# battery_buzzer.net
KiCad netlist of a schematic drawn in EAGLE
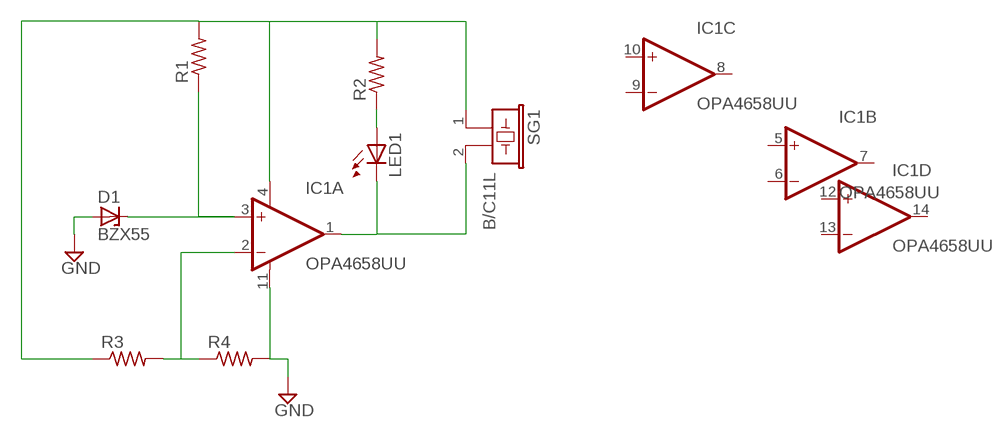
[diagram p0: schematic, sheet 1]

(export (version "E")
  (design (tool "Eeschema 10.0.6"))
  (components
    (comp (ref "D1")
      (value "BZX55")
      (footprint "eagle-import:DO35Z10")
      (libsource (lib "eagle-import") (part "BZX55"))
    )
    (comp (ref "IC1")
      (value "OPA4658UU")
      (footprint "eagle-import:SO14")
      (libsource (lib "eagle-import") (part "OPA4658UU"))
    )
    (comp (ref "LED1")
      (value "LED-FKIT-1206")
      (footprint "eagle-import:FKIT-LED-1206")
      (libsource (lib "eagle-import") (part "LED-FKIT-1206"))
    )
    (comp (ref "R1")
      (value "R-US_R0603")
      (footprint "eagle-import:R0603")
      (libsource (lib "eagle-import") (part "R-US_R0603"))
    )
    (comp (ref "R2")
      (value "R-US_R0603")
      (footprint "eagle-import:R0603")
      (libsource (lib "eagle-import") (part "R-US_R0603"))
    )
    (comp (ref "R3")
      (value "R-US_R0603")
      (footprint "eagle-import:R0603")
      (libsource (lib "eagle-import") (part "R-US_R0603"))
    )
    (comp (ref "R4")
      (value "R-US_R0603")
      (footprint "eagle-import:R0603")
      (libsource (lib "eagle-import") (part "R-US_R0603"))
    )
    (comp (ref "SG1")
      (value "B/C11L")
      (footprint "eagle-import:B_C11L")
      (libsource (lib "eagle-import") (part "B/C11L"))
    )
  )
  (nets
    (net (code "1") (name "GND") (class "Default")
      (node (ref "D1") (pin "A") (pinfunction "A_A") (pintype "passive"))
      (node (ref "IC1") (pin "11") (pinfunction "V-_11") (pintype "power_in"))
      (node (ref "R4") (pin "2") (pinfunction "2_2") (pintype "passive"))
    )
    (net (code "2") (name "Net-(IC1A-+IN)") (class "Default")
      (node (ref "D1") (pin "C") (pinfunction "C_C") (pintype "passive"))
      (node (ref "IC1") (pin "3") (pinfunction "+IN_3") (pintype "input"))
      (node (ref "R1") (pin "1") (pinfunction "1_1") (pintype "passive"))
    )
    (net (code "3") (name "Net-(IC1A--IN)") (class "Default")
      (node (ref "IC1") (pin "2") (pinfunction "-IN_2") (pintype "input"))
      (node (ref "R3") (pin "2") (pinfunction "2_2") (pintype "passive"))
      (node (ref "R4") (pin "1") (pinfunction "1_1") (pintype "passive"))
    )
    (net (code "4") (name "Net-(IC1A-OUT)") (class "Default")
      (node (ref "IC1") (pin "1") (pinfunction "OUT_1") (pintype "output"))
      (node (ref "LED1") (pin "C") (pinfunction "C_C") (pintype "passive"))
      (node (ref "SG1") (pin "2") (pinfunction "2_2") (pintype "passive"))
    )
    (net (code "5") (name "Net-(IC1A-V+)") (class "Default")
      (node (ref "IC1") (pin "4") (pinfunction "V+_4") (pintype "power_in"))
      (node (ref "R1") (pin "2") (pinfunction "2_2") (pintype "passive"))
      (node (ref "R2") (pin "2") (pinfunction "2_2") (pintype "passive"))
      (node (ref "R3") (pin "1") (pinfunction "1_1") (pintype "passive"))
      (node (ref "SG1") (pin "1") (pinfunction "1_1") (pintype "passive"))
    )
    (net (code "6") (name "Net-(LED1-PadA)") (class "Default")
      (node (ref "LED1") (pin "A") (pinfunction "A_A") (pintype "passive"))
      (node (ref "R2") (pin "1") (pinfunction "1_1") (pintype "passive"))
    )
    (net (code "7") (name "unconnected-(IC1B-+IN-Pad5)") (class "Default")
      (node (ref "IC1") (pin "5") (pinfunction "+IN_5") (pintype "input"))
    )
    (net (code "8") (name "unconnected-(IC1B--IN-Pad6)") (class "Default")
      (node (ref "IC1") (pin "6") (pinfunction "-IN_6") (pintype "input"))
    )
    (net (code "9") (name "unconnected-(IC1B-OUT-Pad7)") (class "Default")
      (node (ref "IC1") (pin "7") (pinfunction "OUT_7") (pintype "output"))
    )
    (net (code "10") (name "unconnected-(IC1C-+IN-Pad10)") (class "Default")
      (node (ref "IC1") (pin "10") (pinfunction "+IN_10") (pintype "input"))
    )
    (net (code "11") (name "unconnected-(IC1C--IN-Pad9)") (class "Default")
      (node (ref "IC1") (pin "9") (pinfunction "-IN_9") (pintype "input"))
    )
    (net (code "12") (name "unconnected-(IC1C-OUT-Pad8)") (class "Default")
      (node (ref "IC1") (pin "8") (pinfunction "OUT_8") (pintype "output"))
    )
    (net (code "13") (name "unconnected-(IC1D-+IN-Pad12)") (class "Default")
      (node (ref "IC1") (pin "12") (pinfunction "+IN_12") (pintype "input"))
    )
    (net (code "14") (name "unconnected-(IC1D--IN-Pad13)") (class "Default")
      (node (ref "IC1") (pin "13") (pinfunction "-IN_13") (pintype "input"))
    )
    (net (code "15") (name "unconnected-(IC1D-OUT-Pad14)") (class "Default")
      (node (ref "IC1") (pin "14") (pinfunction "OUT_14") (pintype "output"))
    )
  )
)
